# M160X.net
KiCad netlist of a schematic drawn in EAGLE
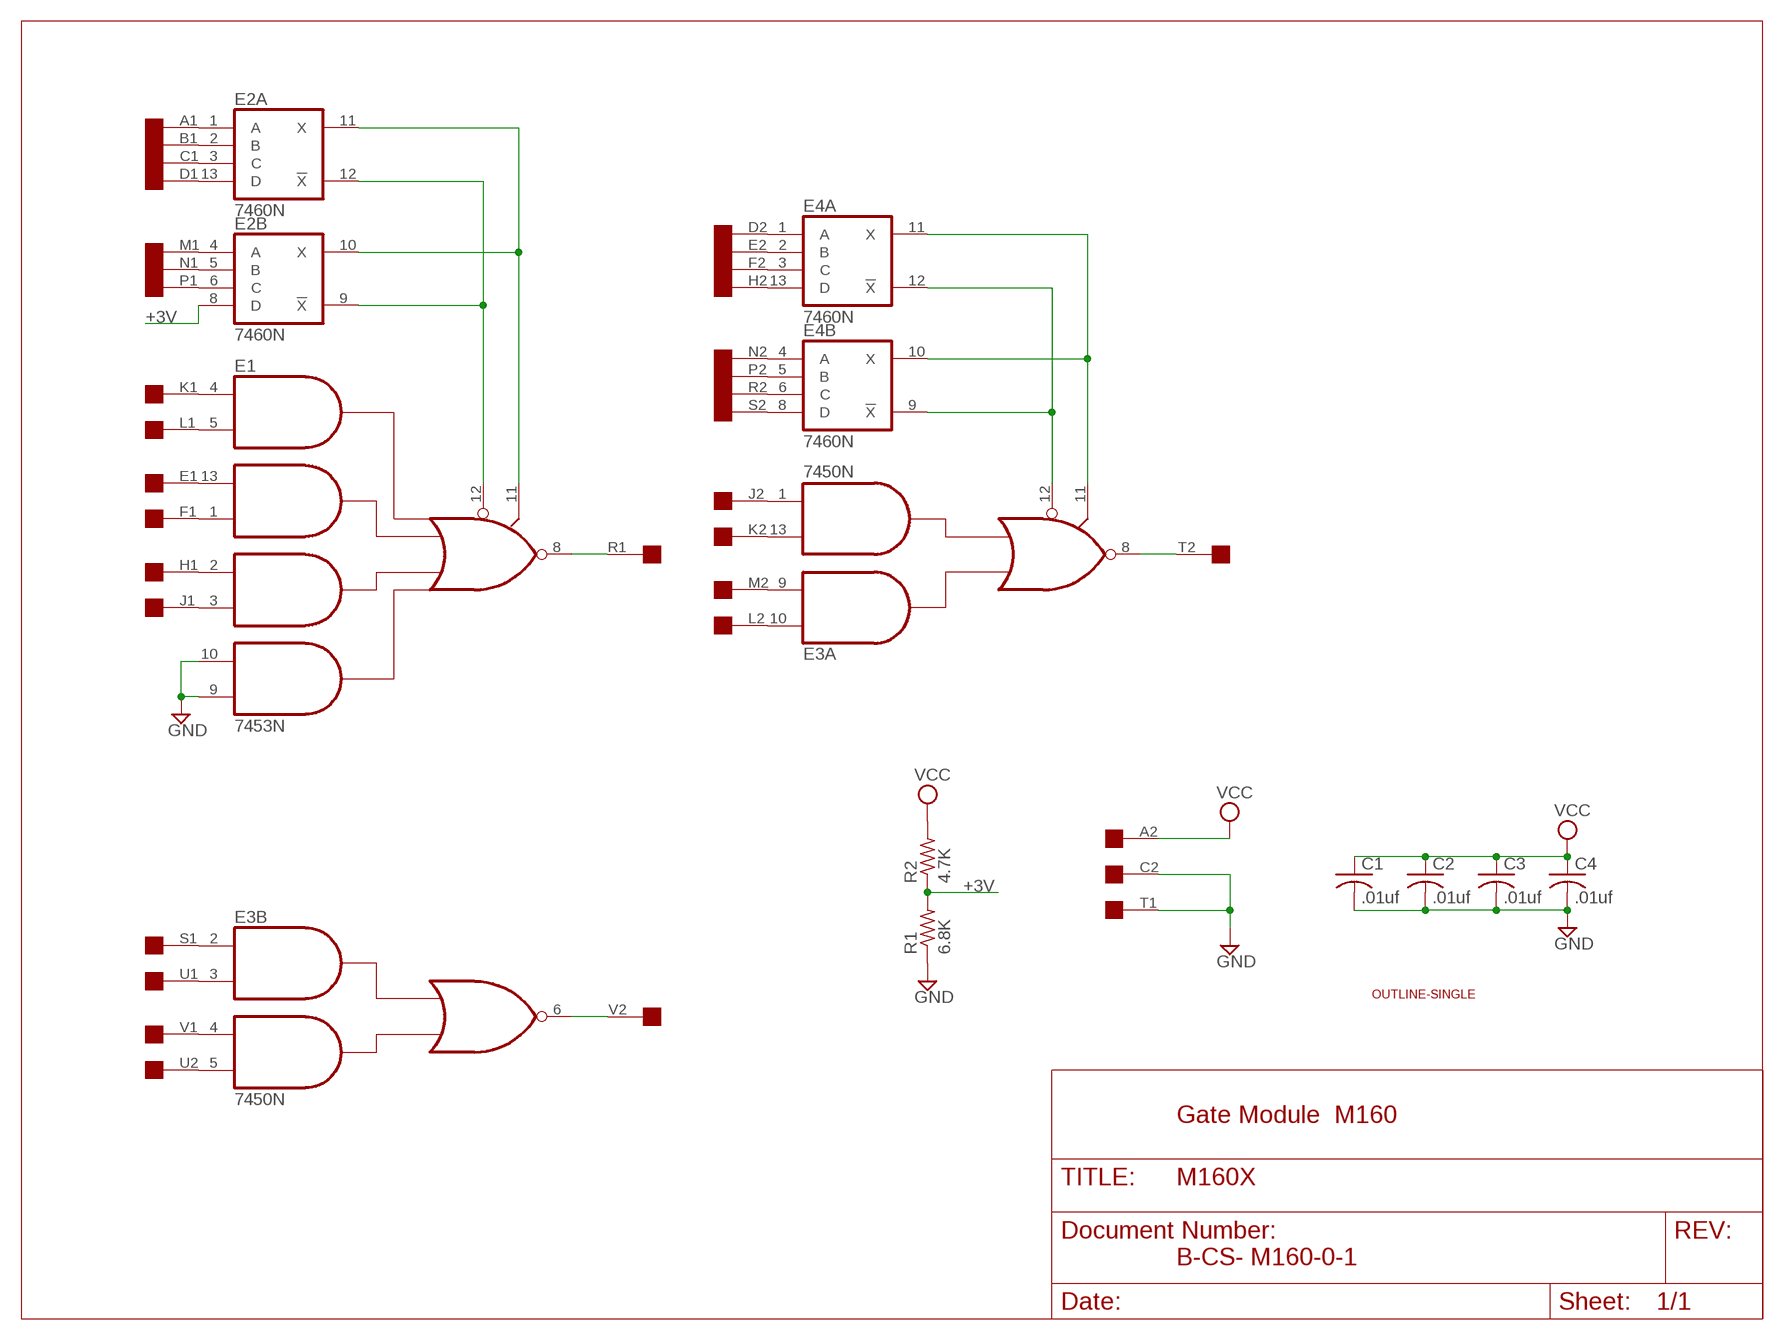
[diagram p0: schematic, sheet 1]

(export (version "E")
  (design (tool "Eeschema 10.0.6"))
  (components
    (comp (ref "C1")
      (value ".01uf")
      (footprint "eagle-import:C050-025X075")
      (libsource (lib "eagle-import") (part "C-US050-025X075"))
    )
    (comp (ref "C2")
      (value ".01uf")
      (footprint "eagle-import:C050-025X075")
      (libsource (lib "eagle-import") (part "C-US050-025X075"))
    )
    (comp (ref "C3")
      (value ".01uf")
      (footprint "eagle-import:C050-025X075")
      (libsource (lib "eagle-import") (part "C-US050-025X075"))
    )
    (comp (ref "C4")
      (value ".01uf")
      (footprint "eagle-import:C050-025X075")
      (libsource (lib "eagle-import") (part "C-US050-025X075"))
    )
    (comp (ref "E1")
      (value "7453N")
      (footprint "eagle-import:DIL14")
      (libsource (lib "eagle-import") (part "7453N"))
    )
    (comp (ref "E2")
      (value "7460N")
      (footprint "eagle-import:DIL14")
      (libsource (lib "eagle-import") (part "7460N"))
    )
    (comp (ref "E3")
      (value "7450N")
      (footprint "eagle-import:DIL14")
      (libsource (lib "eagle-import") (part "7450N"))
    )
    (comp (ref "E4")
      (value "7460N")
      (footprint "eagle-import:DIL14")
      (libsource (lib "eagle-import") (part "7460N"))
    )
    (comp (ref "R1")
      (value "6.8K")
      (footprint "eagle-import:0207_10")
      (libsource (lib "eagle-import") (part "R-US_0207/10"))
    )
    (comp (ref "R2")
      (value "4.7K")
      (footprint "eagle-import:0207_10")
      (libsource (lib "eagle-import") (part "R-US_0207/10"))
    )
    (comp (ref "U$1")
      (value "OUTLINE-SINGLE")
      (footprint "eagle-import:SINGLE")
      (libsource (lib "eagle-import") (part "OUTLINE-SINGLE"))
    )
    (comp (ref "U$4")
      (value "SINGLE")
      (footprint "eagle-import:EDGE-CON2")
      (libsource (lib "eagle-import") (part "SINGLE"))
    )
  )
  (nets
    (net (code "1") (name "/+3V") (class "Default")
      (node (ref "E2") (pin "8") (pinfunction "D_8") (pintype "input"))
      (node (ref "R1") (pin "2") (pinfunction "2_2") (pintype "passive"))
      (node (ref "R2") (pin "1") (pinfunction "1_1") (pintype "passive"))
    )
    (net (code "2") (name "GND") (class "Default")
      (node (ref "C1") (pin "2") (pinfunction "2_2") (pintype "passive"))
      (node (ref "C2") (pin "2") (pinfunction "2_2") (pintype "passive"))
      (node (ref "C3") (pin "2") (pinfunction "2_2") (pintype "passive"))
      (node (ref "C4") (pin "2") (pinfunction "2_2") (pintype "passive"))
      (node (ref "E1") (pin "10") (pinfunction "I7_10") (pintype "input"))
      (node (ref "E1") (pin "9") (pinfunction "I8_9") (pintype "input"))
      (node (ref "R1") (pin "1") (pinfunction "1_1") (pintype "passive"))
      (node (ref "U$4") (pin "C2") (pinfunction "1_C2") (pintype "bidirectional"))
      (node (ref "U$4") (pin "T1") (pinfunction "1_T1") (pintype "bidirectional"))
    )
    (net (code "3") (name "Net-(E1A-I1)") (class "Default")
      (node (ref "E1") (pin "4") (pinfunction "I1_4") (pintype "input"))
      (node (ref "U$4") (pin "K1") (pinfunction "1_K1") (pintype "bidirectional"))
    )
    (net (code "4") (name "Net-(E1A-I2)") (class "Default")
      (node (ref "E1") (pin "5") (pinfunction "I2_5") (pintype "input"))
      (node (ref "U$4") (pin "L1") (pinfunction "1_L1") (pintype "bidirectional"))
    )
    (net (code "5") (name "Net-(E1A-I3)") (class "Default")
      (node (ref "E1") (pin "13") (pinfunction "I3_13") (pintype "input"))
      (node (ref "U$4") (pin "E1") (pinfunction "1_E1") (pintype "bidirectional"))
    )
    (net (code "6") (name "Net-(E1A-I4)") (class "Default")
      (node (ref "E1") (pin "1") (pinfunction "I4_1") (pintype "input"))
      (node (ref "U$4") (pin "F1") (pinfunction "1_F1") (pintype "bidirectional"))
    )
    (net (code "7") (name "Net-(E1A-I5)") (class "Default")
      (node (ref "E1") (pin "2") (pinfunction "I5_2") (pintype "input"))
      (node (ref "U$4") (pin "H1") (pinfunction "1_H1") (pintype "bidirectional"))
    )
    (net (code "8") (name "Net-(E1A-I6)") (class "Default")
      (node (ref "E1") (pin "3") (pinfunction "I6_3") (pintype "input"))
      (node (ref "U$4") (pin "J1") (pinfunction "1_J1") (pintype "bidirectional"))
    )
    (net (code "9") (name "Net-(E1A-I9)") (class "Default")
      (node (ref "E1") (pin "12") (pinfunction "I9_12") (pintype "passive"))
      (node (ref "E2") (pin "12") (pinfunction "~{X}_12") (pintype "output"))
      (node (ref "E2") (pin "9") (pinfunction "~{X}_9") (pintype "output"))
    )
    (net (code "10") (name "Net-(E1A-I10)") (class "Default")
      (node (ref "E1") (pin "11") (pinfunction "I10_11") (pintype "passive"))
      (node (ref "E2") (pin "10") (pinfunction "X_10") (pintype "output"))
      (node (ref "E2") (pin "11") (pinfunction "X_11") (pintype "output"))
    )
    (net (code "11") (name "Net-(E1A-O)") (class "Default")
      (node (ref "E1") (pin "8") (pinfunction "O_8") (pintype "output"))
      (node (ref "U$4") (pin "R1") (pinfunction "1_R1") (pintype "bidirectional"))
    )
    (net (code "12") (name "Net-(E2A-A)") (class "Default")
      (node (ref "E2") (pin "1") (pinfunction "A_1") (pintype "input"))
      (node (ref "U$4") (pin "A1") (pinfunction "1_A1") (pintype "bidirectional"))
    )
    (net (code "13") (name "Net-(E2A-B)") (class "Default")
      (node (ref "E2") (pin "2") (pinfunction "B_2") (pintype "input"))
      (node (ref "U$4") (pin "B1") (pinfunction "1_B1") (pintype "bidirectional"))
    )
    (net (code "14") (name "Net-(E2A-C)") (class "Default")
      (node (ref "E2") (pin "3") (pinfunction "C_3") (pintype "input"))
      (node (ref "U$4") (pin "C1") (pinfunction "1_C1") (pintype "bidirectional"))
    )
    (net (code "15") (name "Net-(E2A-D)") (class "Default")
      (node (ref "E2") (pin "13") (pinfunction "D_13") (pintype "input"))
      (node (ref "U$4") (pin "D1") (pinfunction "1_D1") (pintype "bidirectional"))
    )
    (net (code "16") (name "Net-(E2B-A)") (class "Default")
      (node (ref "E2") (pin "4") (pinfunction "A_4") (pintype "input"))
      (node (ref "U$4") (pin "M1") (pinfunction "1_M1") (pintype "bidirectional"))
    )
    (net (code "17") (name "Net-(E2B-B)") (class "Default")
      (node (ref "E2") (pin "5") (pinfunction "B_5") (pintype "input"))
      (node (ref "U$4") (pin "N1") (pinfunction "1_N1") (pintype "bidirectional"))
    )
    (net (code "18") (name "Net-(E2B-C)") (class "Default")
      (node (ref "E2") (pin "6") (pinfunction "C_6") (pintype "input"))
      (node (ref "U$4") (pin "P1") (pinfunction "1_P1") (pintype "bidirectional"))
    )
    (net (code "19") (name "Net-(E3A-I1)") (class "Default")
      (node (ref "E3") (pin "10") (pinfunction "I1_10") (pintype "input"))
      (node (ref "U$4") (pin "L2") (pinfunction "1_L2") (pintype "bidirectional"))
    )
    (net (code "20") (name "Net-(E3A-I2)") (class "Default")
      (node (ref "E3") (pin "9") (pinfunction "I2_9") (pintype "input"))
      (node (ref "U$4") (pin "M2") (pinfunction "1_M2") (pintype "bidirectional"))
    )
    (net (code "21") (name "Net-(E3A-I3)") (class "Default")
      (node (ref "E3") (pin "13") (pinfunction "I3_13") (pintype "input"))
      (node (ref "U$4") (pin "K2") (pinfunction "1_K2") (pintype "bidirectional"))
    )
    (net (code "22") (name "Net-(E3A-I4)") (class "Default")
      (node (ref "E3") (pin "1") (pinfunction "I4_1") (pintype "input"))
      (node (ref "U$4") (pin "J2") (pinfunction "1_J2") (pintype "bidirectional"))
    )
    (net (code "23") (name "Net-(E3A-I5)") (class "Default")
      (node (ref "E3") (pin "12") (pinfunction "I5_12") (pintype "passive"))
      (node (ref "E4") (pin "12") (pinfunction "~{X}_12") (pintype "output"))
      (node (ref "E4") (pin "9") (pinfunction "~{X}_9") (pintype "output"))
    )
    (net (code "24") (name "Net-(E3A-I6)") (class "Default")
      (node (ref "E3") (pin "11") (pinfunction "I6_11") (pintype "passive"))
      (node (ref "E4") (pin "10") (pinfunction "X_10") (pintype "output"))
      (node (ref "E4") (pin "11") (pinfunction "X_11") (pintype "output"))
    )
    (net (code "25") (name "Net-(E3A-O)") (class "Default")
      (node (ref "E3") (pin "8") (pinfunction "O_8") (pintype "output"))
      (node (ref "U$4") (pin "T2") (pinfunction "1_T2") (pintype "bidirectional"))
    )
    (net (code "26") (name "Net-(E3B-I1)") (class "Default")
      (node (ref "E3") (pin "2") (pinfunction "I1_2") (pintype "input"))
      (node (ref "U$4") (pin "S1") (pinfunction "1_S1") (pintype "bidirectional"))
    )
    (net (code "27") (name "Net-(E3B-I2)") (class "Default")
      (node (ref "E3") (pin "3") (pinfunction "I2_3") (pintype "input"))
      (node (ref "U$4") (pin "U1") (pinfunction "1_U1") (pintype "bidirectional"))
    )
    (net (code "28") (name "Net-(E3B-I3)") (class "Default")
      (node (ref "E3") (pin "4") (pinfunction "I3_4") (pintype "input"))
      (node (ref "U$4") (pin "V1") (pinfunction "1_V1") (pintype "bidirectional"))
    )
    (net (code "29") (name "Net-(E3B-I4)") (class "Default")
      (node (ref "E3") (pin "5") (pinfunction "I4_5") (pintype "input"))
      (node (ref "U$4") (pin "U2") (pinfunction "1_U2") (pintype "bidirectional"))
    )
    (net (code "30") (name "Net-(E3B-O)") (class "Default")
      (node (ref "E3") (pin "6") (pinfunction "O_6") (pintype "output"))
      (node (ref "U$4") (pin "V2") (pinfunction "1_V2") (pintype "bidirectional"))
    )
    (net (code "31") (name "Net-(E4A-A)") (class "Default")
      (node (ref "E4") (pin "1") (pinfunction "A_1") (pintype "input"))
      (node (ref "U$4") (pin "D2") (pinfunction "1_D2") (pintype "bidirectional"))
    )
    (net (code "32") (name "Net-(E4A-B)") (class "Default")
      (node (ref "E4") (pin "2") (pinfunction "B_2") (pintype "input"))
      (node (ref "U$4") (pin "E2") (pinfunction "1_E2") (pintype "bidirectional"))
    )
    (net (code "33") (name "Net-(E4A-C)") (class "Default")
      (node (ref "E4") (pin "3") (pinfunction "C_3") (pintype "input"))
      (node (ref "U$4") (pin "F2") (pinfunction "1_F2") (pintype "bidirectional"))
    )
    (net (code "34") (name "Net-(E4A-D)") (class "Default")
      (node (ref "E4") (pin "13") (pinfunction "D_13") (pintype "input"))
      (node (ref "U$4") (pin "H2") (pinfunction "1_H2") (pintype "bidirectional"))
    )
    (net (code "35") (name "Net-(E4B-A)") (class "Default")
      (node (ref "E4") (pin "4") (pinfunction "A_4") (pintype "input"))
      (node (ref "U$4") (pin "N2") (pinfunction "1_N2") (pintype "bidirectional"))
    )
    (net (code "36") (name "Net-(E4B-B)") (class "Default")
      (node (ref "E4") (pin "5") (pinfunction "B_5") (pintype "input"))
      (node (ref "U$4") (pin "P2") (pinfunction "1_P2") (pintype "bidirectional"))
    )
    (net (code "37") (name "Net-(E4B-C)") (class "Default")
      (node (ref "E4") (pin "6") (pinfunction "C_6") (pintype "input"))
      (node (ref "U$4") (pin "R2") (pinfunction "1_R2") (pintype "bidirectional"))
    )
    (net (code "38") (name "Net-(E4B-D)") (class "Default")
      (node (ref "E4") (pin "8") (pinfunction "D_8") (pintype "input"))
      (node (ref "U$4") (pin "S2") (pinfunction "1_S2") (pintype "bidirectional"))
    )
    (net (code "39") (name "VCC") (class "Default")
      (node (ref "C1") (pin "1") (pinfunction "1_1") (pintype "passive"))
      (node (ref "C2") (pin "1") (pinfunction "1_1") (pintype "passive"))
      (node (ref "C3") (pin "1") (pinfunction "1_1") (pintype "passive"))
      (node (ref "C4") (pin "1") (pinfunction "1_1") (pintype "passive"))
      (node (ref "R2") (pin "2") (pinfunction "2_2") (pintype "passive"))
      (node (ref "U$4") (pin "A2") (pinfunction "1_A2") (pintype "bidirectional"))
    )
  )
)
